# untitled.net
KiCad netlist of a schematic drawn in EAGLE
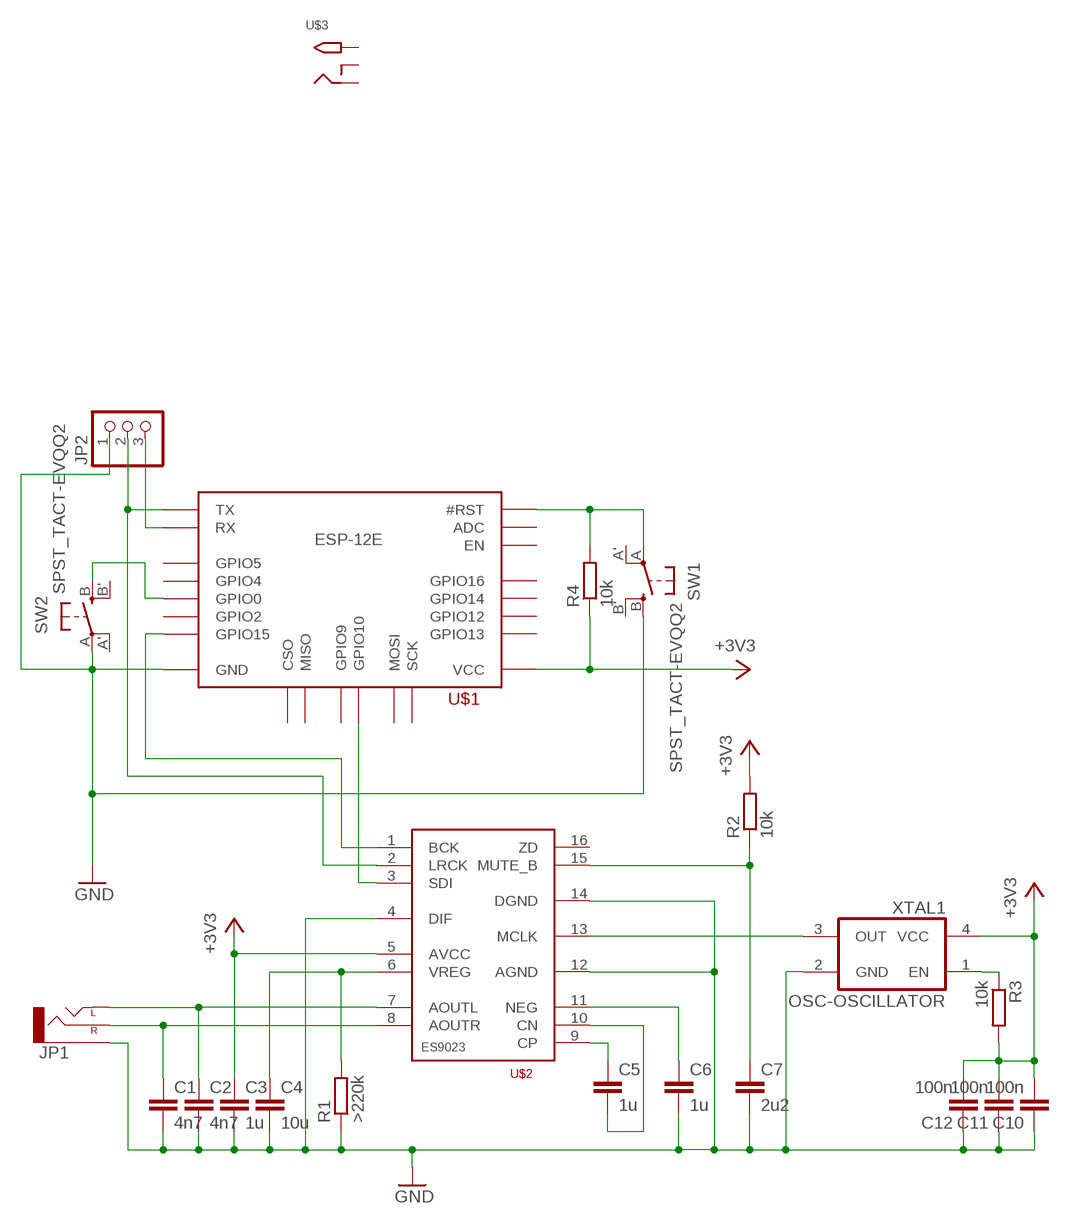
[diagram p0: schematic, sheet 1]

(export (version "E")
  (design (tool "Eeschema 10.0.6"))
  (components
    (comp (ref "C1")
      (value "4n7")
      (footprint "eagle-import:C0805K")
      (libsource (lib "eagle-import") (part "C-EUC0805K"))
    )
    (comp (ref "C2")
      (value "4n7")
      (footprint "eagle-import:C0805K")
      (libsource (lib "eagle-import") (part "C-EUC0805K"))
    )
    (comp (ref "C3")
      (value "1u")
      (footprint "eagle-import:C0805K")
      (libsource (lib "eagle-import") (part "C-EUC0805K"))
    )
    (comp (ref "C4")
      (value "10u")
      (footprint "eagle-import:C0805K")
      (libsource (lib "eagle-import") (part "C-EUC0805K"))
    )
    (comp (ref "C5")
      (value "1u")
      (footprint "eagle-import:C0805K")
      (libsource (lib "eagle-import") (part "C-EUC0805K"))
    )
    (comp (ref "C6")
      (value "1u")
      (footprint "eagle-import:C0805K")
      (libsource (lib "eagle-import") (part "C-EUC0805K"))
    )
    (comp (ref "C7")
      (value "2u2")
      (footprint "eagle-import:C0805K")
      (libsource (lib "eagle-import") (part "C-EUC0805K"))
    )
    (comp (ref "C10")
      (value "100n")
      (footprint "eagle-import:C0805K")
      (libsource (lib "eagle-import") (part "C-EUC0805K"))
    )
    (comp (ref "C11")
      (value "100n")
      (footprint "eagle-import:C0805K")
      (libsource (lib "eagle-import") (part "C-EUC0805K"))
    )
    (comp (ref "C12")
      (value "100n")
      (footprint "eagle-import:C0805K")
      (libsource (lib "eagle-import") (part "C-EUC0805K"))
    )
    (comp (ref "JP1")
      (value "AUDIO-JACKPIN-HOLES")
      (footprint "eagle-import:AUDIO-JACK-HOLES")
      (libsource (lib "eagle-import") (part "AUDIO-JACKPIN-HOLES"))
    )
    (comp (ref "JP2")
      (value "PINHD-1X3")
      (footprint "eagle-import:1X03")
      (libsource (lib "eagle-import") (part "PINHD-1X3"))
    )
    (comp (ref "R1")
      (value ">220k")
      (footprint "eagle-import:M0805")
      (libsource (lib "eagle-import") (part "R-EU_M0805"))
    )
    (comp (ref "R2")
      (value "10k")
      (footprint "eagle-import:M0805")
      (libsource (lib "eagle-import") (part "R-EU_M0805"))
    )
    (comp (ref "R3")
      (value "10k")
      (footprint "eagle-import:M0805")
      (libsource (lib "eagle-import") (part "R-EU_M0805"))
    )
    (comp (ref "R4")
      (value "10k")
      (footprint "eagle-import:M0805")
      (libsource (lib "eagle-import") (part "R-EU_M0805"))
    )
    (comp (ref "SW1")
      (value "SPST_TACT-EVQQ2")
      (footprint "eagle-import:EVQ-Q2")
      (libsource (lib "eagle-import") (part "SPST_TACT-EVQQ2"))
    )
    (comp (ref "SW2")
      (value "SPST_TACT-EVQQ2")
      (footprint "eagle-import:EVQ-Q2")
      (libsource (lib "eagle-import") (part "SPST_TACT-EVQQ2"))
    )
    (comp (ref "U$1")
      (value "ESP-07/12_ESP-12E")
      (footprint "eagle-import:ESP-07_12")
      (libsource (lib "eagle-import") (part "ESP-07/12_ESP-12E"))
    )
    (comp (ref "U$2")
      (value "ES9023-SMD")
      (footprint "eagle-import:SOP16")
      (libsource (lib "eagle-import") (part "ES9023-SMD"))
    )
    (comp (ref "U$3")
      (value "2.1MMJACKTHM")
      (footprint "eagle-import:PJ-102A")
      (libsource (lib "eagle-import") (part "2.1MMJACKTHM"))
    )
    (comp (ref "XTAL1")
      (value "OSC-OSCILLATOR")
      (footprint "eagle-import:OSCILLATOR_7X5_SMD")
      (libsource (lib "eagle-import") (part "OSC-OSCILLATOR"))
    )
  )
  (nets
    (net (code "1") (name "+3V3") (class "Default")
      (node (ref "C10") (pin "2") (pinfunction "2_2") (pintype "passive"))
      (node (ref "C11") (pin "2") (pinfunction "2_2") (pintype "passive"))
      (node (ref "C12") (pin "2") (pinfunction "2_2") (pintype "passive"))
      (node (ref "C3") (pin "1") (pinfunction "1_1") (pintype "passive"))
      (node (ref "R2") (pin "2") (pinfunction "2_2") (pintype "passive"))
      (node (ref "R3") (pin "2") (pinfunction "2_2") (pintype "passive"))
      (node (ref "R4") (pin "1") (pinfunction "1_1") (pintype "passive"))
      (node (ref "U$1") (pin "VCC") (pinfunction "VCC_VCC") (pintype "bidirectional"))
      (node (ref "U$2") (pin "5") (pinfunction "AVCC_5") (pintype "bidirectional"))
      (node (ref "XTAL1") (pin "4") (pinfunction "VCC_4") (pintype "power_in"))
    )
    (net (code "2") (name "GND") (class "Default")
      (node (ref "C1") (pin "2") (pinfunction "2_2") (pintype "passive"))
      (node (ref "C10") (pin "1") (pinfunction "1_1") (pintype "passive"))
      (node (ref "C11") (pin "1") (pinfunction "1_1") (pintype "passive"))
      (node (ref "C12") (pin "1") (pinfunction "1_1") (pintype "passive"))
      (node (ref "C2") (pin "2") (pinfunction "2_2") (pintype "passive"))
      (node (ref "C3") (pin "2") (pinfunction "2_2") (pintype "passive"))
      (node (ref "C4") (pin "2") (pinfunction "2_2") (pintype "passive"))
      (node (ref "C6") (pin "2") (pinfunction "2_2") (pintype "passive"))
      (node (ref "C7") (pin "2") (pinfunction "2_2") (pintype "passive"))
      (node (ref "JP1") (pin "GND") (pinfunction "SLEEVE_GND") (pintype "bidirectional"))
      (node (ref "JP2") (pin "1") (pinfunction "1_1") (pintype "passive"))
      (node (ref "R1") (pin "1") (pinfunction "1_1") (pintype "passive"))
      (node (ref "SW1") (pin "B") (pinfunction "S_B") (pintype "passive"))
      (node (ref "SW2") (pin "A") (pinfunction "P_A") (pintype "passive"))
      (node (ref "U$1") (pin "GND") (pinfunction "GND_GND") (pintype "bidirectional"))
      (node (ref "U$2") (pin "12") (pinfunction "AGND_12") (pintype "bidirectional"))
      (node (ref "U$2") (pin "14") (pinfunction "DGND_14") (pintype "bidirectional"))
      (node (ref "U$2") (pin "4") (pinfunction "DIF_4") (pintype "bidirectional"))
      (node (ref "XTAL1") (pin "2") (pinfunction "GND_2") (pintype "power_in"))
    )
    (net (code "3") (name "Net-(JP1-RIGHT)") (class "Default")
      (node (ref "C1") (pin "1") (pinfunction "1_1") (pintype "passive"))
      (node (ref "JP1") (pin "R+") (pinfunction "RIGHT_R+") (pintype "bidirectional"))
      (node (ref "U$2") (pin "8") (pinfunction "AOUTR_8") (pintype "bidirectional"))
    )
    (net (code "4") (name "Net-(SW1-P)") (class "Default")
      (node (ref "R4") (pin "2") (pinfunction "2_2") (pintype "passive"))
      (node (ref "SW1") (pin "A") (pinfunction "P_A") (pintype "passive"))
      (node (ref "U$1") (pin "REST") (pinfunction "#RST_REST") (pintype "bidirectional"))
    )
    (net (code "5") (name "Net-(SW2-S)") (class "Default")
      (node (ref "SW2") (pin "B") (pinfunction "S_B") (pintype "passive"))
      (node (ref "U$1") (pin "GPIO0") (pinfunction "GPIO0_GPIO0") (pintype "bidirectional"))
    )
    (net (code "6") (name "Net-(U$1-RX)") (class "Default")
      (node (ref "JP2") (pin "3") (pinfunction "3_3") (pintype "passive"))
      (node (ref "U$1") (pin "RXD0") (pinfunction "RX_RXD0") (pintype "bidirectional"))
    )
    (net (code "7") (name "Net-(U$1-TX)") (class "Default")
      (node (ref "JP2") (pin "2") (pinfunction "2_2") (pintype "passive"))
      (node (ref "U$1") (pin "TXD0") (pinfunction "TX_TXD0") (pintype "bidirectional"))
      (node (ref "U$2") (pin "2") (pinfunction "LRCK_2") (pintype "bidirectional"))
    )
    (net (code "8") (name "Net-(U$2-AOUTL)") (class "Default")
      (node (ref "C2") (pin "1") (pinfunction "1_1") (pintype "passive"))
      (node (ref "JP1") (pin "L1-") (pinfunction "LEFT_L1-") (pintype "bidirectional"))
      (node (ref "JP1") (pin "L2-") (pinfunction "LEFT_L2-") (pintype "bidirectional"))
      (node (ref "U$2") (pin "7") (pinfunction "AOUTL_7") (pintype "bidirectional"))
    )
    (net (code "9") (name "Net-(U$2-BCK)") (class "Default")
      (node (ref "U$1") (pin "GPIO15") (pinfunction "GPIO15_GPIO15") (pintype "bidirectional"))
      (node (ref "U$2") (pin "1") (pinfunction "BCK_1") (pintype "bidirectional"))
    )
    (net (code "10") (name "Net-(U$2-CN)") (class "Default")
      (node (ref "C5") (pin "2") (pinfunction "2_2") (pintype "passive"))
      (node (ref "U$2") (pin "10") (pinfunction "CN_10") (pintype "bidirectional"))
    )
    (net (code "11") (name "Net-(U$2-CP)") (class "Default")
      (node (ref "C5") (pin "1") (pinfunction "1_1") (pintype "passive"))
      (node (ref "U$2") (pin "9") (pinfunction "CP_9") (pintype "bidirectional"))
    )
    (net (code "12") (name "Net-(U$2-MCLK)") (class "Default")
      (node (ref "U$2") (pin "13") (pinfunction "MCLK_13") (pintype "bidirectional"))
      (node (ref "XTAL1") (pin "3") (pinfunction "OUT_3") (pintype "output"))
    )
    (net (code "13") (name "Net-(U$2-MUTE_B)") (class "Default")
      (node (ref "C7") (pin "1") (pinfunction "1_1") (pintype "passive"))
      (node (ref "R2") (pin "1") (pinfunction "1_1") (pintype "passive"))
      (node (ref "U$2") (pin "15") (pinfunction "MUTE_B_15") (pintype "bidirectional"))
    )
    (net (code "14") (name "Net-(U$2-NEG)") (class "Default")
      (node (ref "C6") (pin "1") (pinfunction "1_1") (pintype "passive"))
      (node (ref "U$2") (pin "11") (pinfunction "NEG_11") (pintype "bidirectional"))
    )
    (net (code "15") (name "Net-(U$2-SDI)") (class "Default")
      (node (ref "U$1") (pin "GPIO10") (pinfunction "GPIO10_GPIO10") (pintype "bidirectional"))
      (node (ref "U$2") (pin "3") (pinfunction "SDI_3") (pintype "bidirectional"))
    )
    (net (code "16") (name "Net-(U$2-VREG)") (class "Default")
      (node (ref "C4") (pin "1") (pinfunction "1_1") (pintype "passive"))
      (node (ref "R1") (pin "2") (pinfunction "2_2") (pintype "passive"))
      (node (ref "U$2") (pin "6") (pinfunction "VREG_6") (pintype "bidirectional"))
    )
    (net (code "17") (name "Net-(XTAL1-EN)") (class "Default")
      (node (ref "R3") (pin "1") (pinfunction "1_1") (pintype "passive"))
      (node (ref "XTAL1") (pin "1") (pinfunction "EN_1") (pintype "input"))
    )
    (net (code "18") (name "unconnected-(SW1-P1-PadA')") (class "Default")
      (node (ref "SW1") (pin "A'") (pinfunction "P1_A'") (pintype "passive"))
    )
    (net (code "19") (name "unconnected-(SW1-S1-PadB')") (class "Default")
      (node (ref "SW1") (pin "B'") (pinfunction "S1_B'") (pintype "passive"))
    )
    (net (code "20") (name "unconnected-(SW2-P1-PadA')") (class "Default")
      (node (ref "SW2") (pin "A'") (pinfunction "P1_A'") (pintype "passive"))
    )
    (net (code "21") (name "unconnected-(SW2-S1-PadB')") (class "Default")
      (node (ref "SW2") (pin "B'") (pinfunction "S1_B'") (pintype "passive"))
    )
    (net (code "22") (name "unconnected-(U$1-PadADC)") (class "Default")
      (node (ref "U$1") (pin "ADC") (pinfunction "ADC_ADC") (pintype "bidirectional"))
    )
    (net (code "23") (name "unconnected-(U$1-PadCSO)") (class "Default")
      (node (ref "U$1") (pin "CSO") (pinfunction "CSO_CSO") (pintype "bidirectional"))
    )
    (net (code "24") (name "unconnected-(U$1-PadEN)") (class "Default")
      (node (ref "U$1") (pin "EN") (pinfunction "EN_EN") (pintype "bidirectional"))
    )
    (net (code "25") (name "unconnected-(U$1-PadGPIO2)") (class "Default")
      (node (ref "U$1") (pin "GPIO2") (pinfunction "GPIO2_GPIO2") (pintype "bidirectional"))
    )
    (net (code "26") (name "unconnected-(U$1-PadGPIO4)") (class "Default")
      (node (ref "U$1") (pin "GPIO4") (pinfunction "GPIO4_GPIO4") (pintype "bidirectional"))
    )
    (net (code "27") (name "unconnected-(U$1-PadGPIO5)") (class "Default")
      (node (ref "U$1") (pin "GPIO5") (pinfunction "GPIO5_GPIO5") (pintype "bidirectional"))
    )
    (net (code "28") (name "unconnected-(U$1-PadGPIO9)") (class "Default")
      (node (ref "U$1") (pin "GPIO9") (pinfunction "GPIO9_GPIO9") (pintype "bidirectional"))
    )
    (net (code "29") (name "unconnected-(U$1-PadGPIO12)") (class "Default")
      (node (ref "U$1") (pin "GPIO12") (pinfunction "GPIO12_GPIO12") (pintype "bidirectional"))
    )
    (net (code "30") (name "unconnected-(U$1-PadGPIO13)") (class "Default")
      (node (ref "U$1") (pin "GPIO13") (pinfunction "GPIO13_GPIO13") (pintype "bidirectional"))
    )
    (net (code "31") (name "unconnected-(U$1-PadGPIO14)") (class "Default")
      (node (ref "U$1") (pin "GPIO14") (pinfunction "GPIO14_GPIO14") (pintype "bidirectional"))
    )
    (net (code "32") (name "unconnected-(U$1-PadGPIO16)") (class "Default")
      (node (ref "U$1") (pin "GPIO16") (pinfunction "GPIO16_GPIO16") (pintype "bidirectional"))
    )
    (net (code "33") (name "unconnected-(U$1-PadMISO)") (class "Default")
      (node (ref "U$1") (pin "MISO") (pinfunction "MISO_MISO") (pintype "bidirectional"))
    )
    (net (code "34") (name "unconnected-(U$1-PadMOSI)") (class "Default")
      (node (ref "U$1") (pin "MOSI") (pinfunction "MOSI_MOSI") (pintype "bidirectional"))
    )
    (net (code "35") (name "unconnected-(U$1-SCK-PadSCLK)") (class "Default")
      (node (ref "U$1") (pin "SCLK") (pinfunction "SCK_SCLK") (pintype "bidirectional"))
    )
    (net (code "36") (name "unconnected-(U$2-ZD-Pad16)") (class "Default")
      (node (ref "U$2") (pin "16") (pinfunction "ZD_16") (pintype "bidirectional"))
    )
    (net (code "37") (name "unconnected-(U$3-PadRING)") (class "Default")
      (node (ref "U$3") (pin "RING") (pinfunction "RING_RING") (pintype "bidirectional"))
    )
    (net (code "38") (name "unconnected-(U$3-PadRING_SW)") (class "Default")
      (node (ref "U$3") (pin "RING_SW") (pinfunction "RING_SW_RING_SW") (pintype "bidirectional"))
    )
    (net (code "39") (name "unconnected-(U$3-PadTIP)") (class "Default")
      (node (ref "U$3") (pin "TIP") (pinfunction "TIP_TIP") (pintype "bidirectional"))
    )
  )
)
